# sapflow_pcb_v1.net
KiCad netlist of a schematic drawn in EAGLE
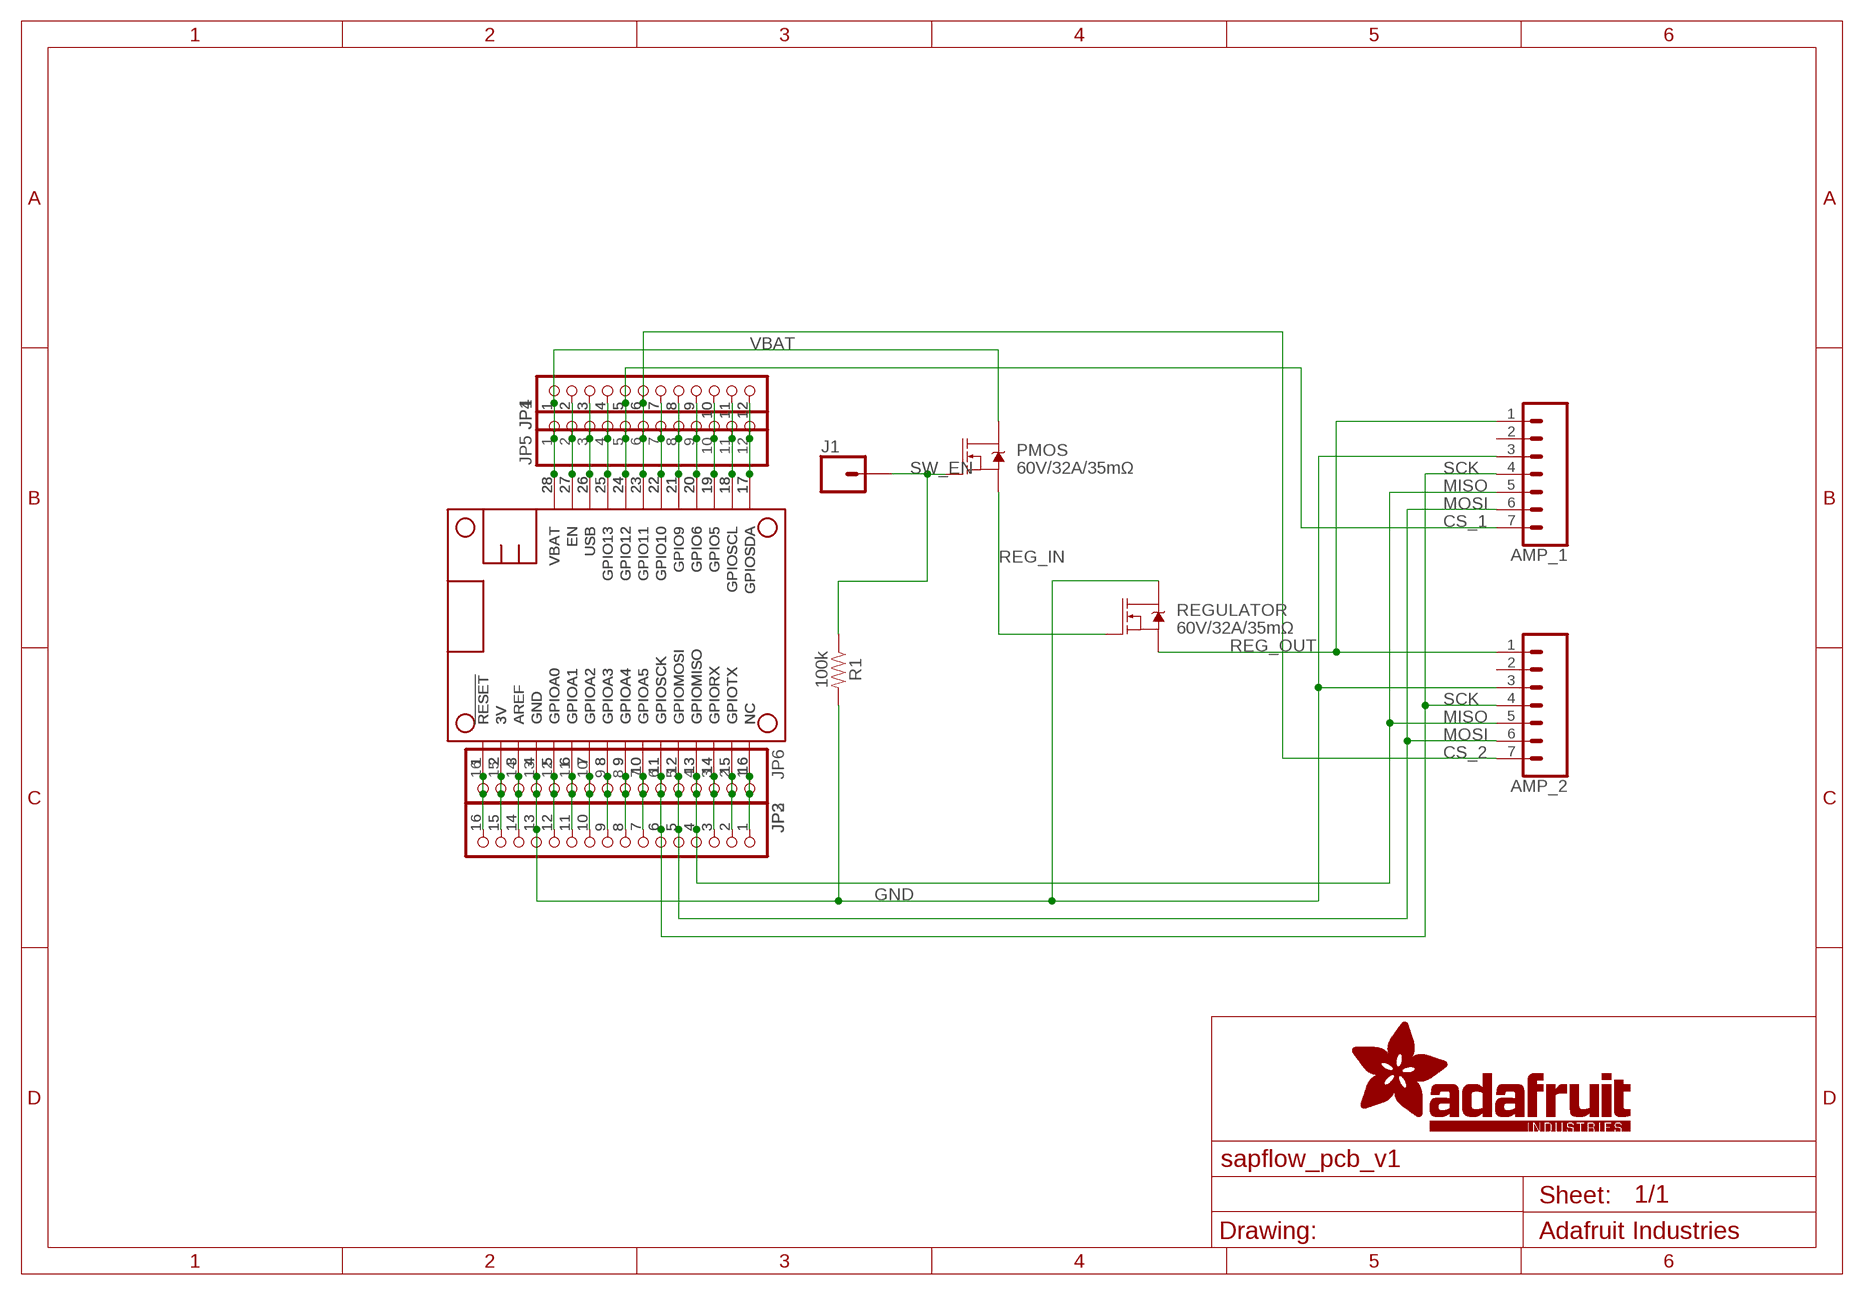
[diagram p0: schematic, sheet 1]

(export (version "E")
  (design (tool "Eeschema 10.0.6"))
  (components
    (comp (ref "AMP_1")
      (value "CONN_07")
      (footprint "eagle-import:1X07")
      (libsource (lib "eagle-import") (part "CONN_07"))
    )
    (comp (ref "AMP_2")
      (value "CONN_07")
      (footprint "eagle-import:1X07")
      (libsource (lib "eagle-import") (part "CONN_07"))
    )
    (comp (ref "J1")
      (value "CONN_01")
      (footprint "eagle-import:1X01")
      (libsource (lib "eagle-import") (part "CONN_01"))
    )
    (comp (ref "JP1")
      (value "HEADER-1X1276MIL")
      (footprint "eagle-import:1X12_ROUND_76MIL")
      (libsource (lib "eagle-import") (part "HEADER-1X1276MIL"))
    )
    (comp (ref "JP2")
      (value "HEADER-1X16_76MIL")
      (footprint "eagle-import:1X16_ROUND_76MIL")
      (libsource (lib "eagle-import") (part "HEADER-1X16_76MIL"))
    )
    (comp (ref "JP3")
      (value "HEADER-1X16_76MIL")
      (footprint "eagle-import:1X16_ROUND_76MIL")
      (libsource (lib "eagle-import") (part "HEADER-1X16_76MIL"))
    )
    (comp (ref "JP4")
      (value "HEADER-1X1276MIL")
      (footprint "eagle-import:1X12_ROUND_76MIL")
      (libsource (lib "eagle-import") (part "HEADER-1X1276MIL"))
    )
    (comp (ref "JP5")
      (value "HEADER-1X1276MIL")
      (footprint "eagle-import:1X12_ROUND_76MIL")
      (libsource (lib "eagle-import") (part "HEADER-1X1276MIL"))
    )
    (comp (ref "JP6")
      (value "HEADER-1X16_76MIL")
      (footprint "eagle-import:1X16_ROUND_76MIL")
      (libsource (lib "eagle-import") (part "HEADER-1X16_76MIL"))
    )
    (comp (ref "MS1")
      (value "FEATHERWING_NODIM")
      (footprint "eagle-import:FEATHERWING_DIM")
      (libsource (lib "eagle-import") (part "FEATHERWING_NODIM"))
    )
    (comp (ref "MS2")
      (value "FEATHERWING_NODIM")
      (footprint "eagle-import:FEATHERWING_DIM")
      (libsource (lib "eagle-import") (part "FEATHERWING_NODIM"))
    )
    (comp (ref "MS3")
      (value "FEATHERWING_NODIM")
      (footprint "eagle-import:FEATHERWING_DIM")
      (libsource (lib "eagle-import") (part "FEATHERWING_NODIM"))
    )
    (comp (ref "PMOS")
      (value "60V/32A/35mΩ")
      (footprint "eagle-import:TO220V")
      (libsource (lib "eagle-import") (part "MOSFET-NCH-FQP30N06L"))
    )
    (comp (ref "R1")
      (value "100k")
      (footprint "eagle-import:AXIAL-0.3")
      (libsource (lib "eagle-import") (part "100KOHM-HORIZ-1/4W-1%"))
    )
    (comp (ref "REGULATOR")
      (value "60V/32A/35mΩ")
      (footprint "eagle-import:TO220V")
      (libsource (lib "eagle-import") (part "MOSFET-NCH-FQP30N06L"))
    )
  )
  (nets
    (net (code "1") (name "/CS_1") (class "Default")
      (node (ref "AMP_1") (pin "7") (pinfunction "7_7") (pintype "passive"))
      (node (ref "JP1") (pin "5") (pinfunction "5_5") (pintype "passive"))
      (node (ref "JP4") (pin "5") (pinfunction "5_5") (pintype "passive"))
      (node (ref "JP5") (pin "5") (pinfunction "5_5") (pintype "passive"))
      (node (ref "MS1") (pin "24") (pinfunction "GPIO12_24") (pintype "bidirectional"))
      (node (ref "MS2") (pin "24") (pinfunction "GPIO12_24") (pintype "bidirectional"))
      (node (ref "MS3") (pin "24") (pinfunction "GPIO12_24") (pintype "bidirectional"))
    )
    (net (code "2") (name "/CS_2") (class "Default")
      (node (ref "AMP_2") (pin "7") (pinfunction "7_7") (pintype "passive"))
      (node (ref "JP1") (pin "6") (pinfunction "6_6") (pintype "passive"))
      (node (ref "JP4") (pin "6") (pinfunction "6_6") (pintype "passive"))
      (node (ref "JP5") (pin "6") (pinfunction "6_6") (pintype "passive"))
      (node (ref "MS1") (pin "23") (pinfunction "GPIO11_23") (pintype "bidirectional"))
      (node (ref "MS2") (pin "23") (pinfunction "GPIO11_23") (pintype "bidirectional"))
      (node (ref "MS3") (pin "23") (pinfunction "GPIO11_23") (pintype "bidirectional"))
    )
    (net (code "3") (name "/GND") (class "Default")
      (node (ref "AMP_1") (pin "3") (pinfunction "3_3") (pintype "passive"))
      (node (ref "AMP_2") (pin "3") (pinfunction "3_3") (pintype "passive"))
      (node (ref "JP2") (pin "13") (pinfunction "13_13") (pintype "passive"))
      (node (ref "JP3") (pin "13") (pinfunction "13_13") (pintype "passive"))
      (node (ref "JP6") (pin "13") (pinfunction "13_13") (pintype "passive"))
      (node (ref "MS1") (pin "4") (pinfunction "GND_4") (pintype "power_in"))
      (node (ref "MS2") (pin "4") (pinfunction "GND_4") (pintype "power_in"))
      (node (ref "MS3") (pin "4") (pinfunction "GND_4") (pintype "power_in"))
      (node (ref "R1") (pin "P$2") (pinfunction "2_P$2") (pintype "passive"))
      (node (ref "REGULATOR") (pin "2") (pinfunction "D_2") (pintype "bidirectional"))
    )
    (net (code "4") (name "/MISO") (class "Default")
      (node (ref "AMP_1") (pin "5") (pinfunction "5_5") (pintype "passive"))
      (node (ref "AMP_2") (pin "5") (pinfunction "5_5") (pintype "passive"))
      (node (ref "JP2") (pin "4") (pinfunction "4_4") (pintype "passive"))
      (node (ref "JP3") (pin "4") (pinfunction "4_4") (pintype "passive"))
      (node (ref "JP6") (pin "4") (pinfunction "4_4") (pintype "passive"))
      (node (ref "MS1") (pin "13") (pinfunction "GPIOMISO_13") (pintype "bidirectional"))
      (node (ref "MS2") (pin "13") (pinfunction "GPIOMISO_13") (pintype "bidirectional"))
      (node (ref "MS3") (pin "13") (pinfunction "GPIOMISO_13") (pintype "bidirectional"))
    )
    (net (code "5") (name "/MOSI") (class "Default")
      (node (ref "AMP_1") (pin "6") (pinfunction "6_6") (pintype "passive"))
      (node (ref "AMP_2") (pin "6") (pinfunction "6_6") (pintype "passive"))
      (node (ref "JP2") (pin "5") (pinfunction "5_5") (pintype "passive"))
      (node (ref "JP3") (pin "5") (pinfunction "5_5") (pintype "passive"))
      (node (ref "JP6") (pin "5") (pinfunction "5_5") (pintype "passive"))
      (node (ref "MS1") (pin "12") (pinfunction "GPIOMOSI_12") (pintype "bidirectional"))
      (node (ref "MS2") (pin "12") (pinfunction "GPIOMOSI_12") (pintype "bidirectional"))
      (node (ref "MS3") (pin "12") (pinfunction "GPIOMOSI_12") (pintype "bidirectional"))
    )
    (net (code "6") (name "/REG_IN") (class "Default")
      (node (ref "PMOS") (pin "3") (pinfunction "S_3") (pintype "bidirectional"))
      (node (ref "REGULATOR") (pin "1") (pinfunction "G_1") (pintype "bidirectional"))
    )
    (net (code "7") (name "/REG_OUT") (class "Default")
      (node (ref "AMP_1") (pin "1") (pinfunction "1_1") (pintype "passive"))
      (node (ref "AMP_2") (pin "1") (pinfunction "1_1") (pintype "passive"))
      (node (ref "REGULATOR") (pin "3") (pinfunction "S_3") (pintype "bidirectional"))
    )
    (net (code "8") (name "/SCK") (class "Default")
      (node (ref "AMP_1") (pin "4") (pinfunction "4_4") (pintype "passive"))
      (node (ref "AMP_2") (pin "4") (pinfunction "4_4") (pintype "passive"))
      (node (ref "JP2") (pin "6") (pinfunction "6_6") (pintype "passive"))
      (node (ref "JP3") (pin "6") (pinfunction "6_6") (pintype "passive"))
      (node (ref "JP6") (pin "6") (pinfunction "6_6") (pintype "passive"))
      (node (ref "MS1") (pin "11") (pinfunction "GPIOSCK_11") (pintype "bidirectional"))
      (node (ref "MS2") (pin "11") (pinfunction "GPIOSCK_11") (pintype "bidirectional"))
      (node (ref "MS3") (pin "11") (pinfunction "GPIOSCK_11") (pintype "bidirectional"))
    )
    (net (code "9") (name "/SW_EN") (class "Default")
      (node (ref "J1") (pin "1") (pinfunction "1_1") (pintype "passive"))
      (node (ref "PMOS") (pin "1") (pinfunction "G_1") (pintype "bidirectional"))
      (node (ref "R1") (pin "P$1") (pinfunction "1_P$1") (pintype "passive"))
    )
    (net (code "10") (name "/VBAT") (class "Default")
      (node (ref "JP1") (pin "1") (pinfunction "1_1") (pintype "passive"))
      (node (ref "JP4") (pin "1") (pinfunction "1_1") (pintype "passive"))
      (node (ref "JP5") (pin "1") (pinfunction "1_1") (pintype "passive"))
      (node (ref "MS1") (pin "28") (pinfunction "VBAT_28") (pintype "power_in"))
      (node (ref "MS2") (pin "28") (pinfunction "VBAT_28") (pintype "power_in"))
      (node (ref "MS3") (pin "28") (pinfunction "VBAT_28") (pintype "power_in"))
      (node (ref "PMOS") (pin "2") (pinfunction "D_2") (pintype "bidirectional"))
    )
    (net (code "11") (name "Net-(MS1-3V)") (class "Default")
      (node (ref "JP2") (pin "15") (pinfunction "15_15") (pintype "passive"))
      (node (ref "JP3") (pin "15") (pinfunction "15_15") (pintype "passive"))
      (node (ref "JP6") (pin "15") (pinfunction "15_15") (pintype "passive"))
      (node (ref "MS1") (pin "2") (pinfunction "3V_2") (pintype "power_in"))
      (node (ref "MS2") (pin "2") (pinfunction "3V_2") (pintype "power_in"))
      (node (ref "MS3") (pin "2") (pinfunction "3V_2") (pintype "power_in"))
    )
    (net (code "12") (name "Net-(MS1-AREF)") (class "Default")
      (node (ref "JP2") (pin "14") (pinfunction "14_14") (pintype "passive"))
      (node (ref "JP3") (pin "14") (pinfunction "14_14") (pintype "passive"))
      (node (ref "JP6") (pin "14") (pinfunction "14_14") (pintype "passive"))
      (node (ref "MS1") (pin "3") (pinfunction "AREF_3") (pintype "passive"))
      (node (ref "MS2") (pin "3") (pinfunction "AREF_3") (pintype "passive"))
      (node (ref "MS3") (pin "3") (pinfunction "AREF_3") (pintype "passive"))
    )
    (net (code "13") (name "Net-(MS1-EN)") (class "Default")
      (node (ref "JP1") (pin "2") (pinfunction "2_2") (pintype "passive"))
      (node (ref "JP4") (pin "2") (pinfunction "2_2") (pintype "passive"))
      (node (ref "JP5") (pin "2") (pinfunction "2_2") (pintype "passive"))
      (node (ref "MS1") (pin "27") (pinfunction "EN_27") (pintype "passive"))
      (node (ref "MS2") (pin "27") (pinfunction "EN_27") (pintype "passive"))
      (node (ref "MS3") (pin "27") (pinfunction "EN_27") (pintype "passive"))
    )
    (net (code "14") (name "Net-(MS1-GPIO5)") (class "Default")
      (node (ref "JP1") (pin "10") (pinfunction "10_10") (pintype "passive"))
      (node (ref "JP4") (pin "10") (pinfunction "10_10") (pintype "passive"))
      (node (ref "JP5") (pin "10") (pinfunction "10_10") (pintype "passive"))
      (node (ref "MS1") (pin "19") (pinfunction "GPIO5_19") (pintype "bidirectional"))
      (node (ref "MS2") (pin "19") (pinfunction "GPIO5_19") (pintype "bidirectional"))
      (node (ref "MS3") (pin "19") (pinfunction "GPIO5_19") (pintype "bidirectional"))
    )
    (net (code "15") (name "Net-(MS1-GPIO6)") (class "Default")
      (node (ref "JP1") (pin "9") (pinfunction "9_9") (pintype "passive"))
      (node (ref "JP4") (pin "9") (pinfunction "9_9") (pintype "passive"))
      (node (ref "JP5") (pin "9") (pinfunction "9_9") (pintype "passive"))
      (node (ref "MS1") (pin "20") (pinfunction "GPIO6_20") (pintype "bidirectional"))
      (node (ref "MS2") (pin "20") (pinfunction "GPIO6_20") (pintype "bidirectional"))
      (node (ref "MS3") (pin "20") (pinfunction "GPIO6_20") (pintype "bidirectional"))
    )
    (net (code "16") (name "Net-(MS1-GPIO9)") (class "Default")
      (node (ref "JP1") (pin "8") (pinfunction "8_8") (pintype "passive"))
      (node (ref "JP4") (pin "8") (pinfunction "8_8") (pintype "passive"))
      (node (ref "JP5") (pin "8") (pinfunction "8_8") (pintype "passive"))
      (node (ref "MS1") (pin "21") (pinfunction "GPIO9_21") (pintype "bidirectional"))
      (node (ref "MS2") (pin "21") (pinfunction "GPIO9_21") (pintype "bidirectional"))
      (node (ref "MS3") (pin "21") (pinfunction "GPIO9_21") (pintype "bidirectional"))
    )
    (net (code "17") (name "Net-(MS1-GPIO10)") (class "Default")
      (node (ref "JP1") (pin "7") (pinfunction "7_7") (pintype "passive"))
      (node (ref "JP4") (pin "7") (pinfunction "7_7") (pintype "passive"))
      (node (ref "JP5") (pin "7") (pinfunction "7_7") (pintype "passive"))
      (node (ref "MS1") (pin "22") (pinfunction "GPIO10_22") (pintype "bidirectional"))
      (node (ref "MS2") (pin "22") (pinfunction "GPIO10_22") (pintype "bidirectional"))
      (node (ref "MS3") (pin "22") (pinfunction "GPIO10_22") (pintype "bidirectional"))
    )
    (net (code "18") (name "Net-(MS1-GPIO13)") (class "Default")
      (node (ref "JP1") (pin "4") (pinfunction "4_4") (pintype "passive"))
      (node (ref "JP4") (pin "4") (pinfunction "4_4") (pintype "passive"))
      (node (ref "JP5") (pin "4") (pinfunction "4_4") (pintype "passive"))
      (node (ref "MS1") (pin "25") (pinfunction "GPIO13_25") (pintype "bidirectional"))
      (node (ref "MS2") (pin "25") (pinfunction "GPIO13_25") (pintype "bidirectional"))
      (node (ref "MS3") (pin "25") (pinfunction "GPIO13_25") (pintype "bidirectional"))
    )
    (net (code "19") (name "Net-(MS1-GPIOA0)") (class "Default")
      (node (ref "JP2") (pin "12") (pinfunction "12_12") (pintype "passive"))
      (node (ref "JP3") (pin "12") (pinfunction "12_12") (pintype "passive"))
      (node (ref "JP6") (pin "12") (pinfunction "12_12") (pintype "passive"))
      (node (ref "MS1") (pin "5") (pinfunction "GPIOA0_5") (pintype "bidirectional"))
      (node (ref "MS2") (pin "5") (pinfunction "GPIOA0_5") (pintype "bidirectional"))
      (node (ref "MS3") (pin "5") (pinfunction "GPIOA0_5") (pintype "bidirectional"))
    )
    (net (code "20") (name "Net-(MS1-GPIOA1)") (class "Default")
      (node (ref "JP2") (pin "11") (pinfunction "11_11") (pintype "passive"))
      (node (ref "JP3") (pin "11") (pinfunction "11_11") (pintype "passive"))
      (node (ref "JP6") (pin "11") (pinfunction "11_11") (pintype "passive"))
      (node (ref "MS1") (pin "6") (pinfunction "GPIOA1_6") (pintype "bidirectional"))
      (node (ref "MS2") (pin "6") (pinfunction "GPIOA1_6") (pintype "bidirectional"))
      (node (ref "MS3") (pin "6") (pinfunction "GPIOA1_6") (pintype "bidirectional"))
    )
    (net (code "21") (name "Net-(MS1-GPIOA2)") (class "Default")
      (node (ref "JP2") (pin "10") (pinfunction "10_10") (pintype "passive"))
      (node (ref "JP3") (pin "10") (pinfunction "10_10") (pintype "passive"))
      (node (ref "JP6") (pin "10") (pinfunction "10_10") (pintype "passive"))
      (node (ref "MS1") (pin "7") (pinfunction "GPIOA2_7") (pintype "bidirectional"))
      (node (ref "MS2") (pin "7") (pinfunction "GPIOA2_7") (pintype "bidirectional"))
      (node (ref "MS3") (pin "7") (pinfunction "GPIOA2_7") (pintype "bidirectional"))
    )
    (net (code "22") (name "Net-(MS1-GPIOA3)") (class "Default")
      (node (ref "JP2") (pin "9") (pinfunction "9_9") (pintype "passive"))
      (node (ref "JP3") (pin "9") (pinfunction "9_9") (pintype "passive"))
      (node (ref "JP6") (pin "9") (pinfunction "9_9") (pintype "passive"))
      (node (ref "MS1") (pin "8") (pinfunction "GPIOA3_8") (pintype "bidirectional"))
      (node (ref "MS2") (pin "8") (pinfunction "GPIOA3_8") (pintype "bidirectional"))
      (node (ref "MS3") (pin "8") (pinfunction "GPIOA3_8") (pintype "bidirectional"))
    )
    (net (code "23") (name "Net-(MS1-GPIOA4)") (class "Default")
      (node (ref "JP2") (pin "8") (pinfunction "8_8") (pintype "passive"))
      (node (ref "JP3") (pin "8") (pinfunction "8_8") (pintype "passive"))
      (node (ref "JP6") (pin "8") (pinfunction "8_8") (pintype "passive"))
      (node (ref "MS1") (pin "9") (pinfunction "GPIOA4_9") (pintype "bidirectional"))
      (node (ref "MS2") (pin "9") (pinfunction "GPIOA4_9") (pintype "bidirectional"))
      (node (ref "MS3") (pin "9") (pinfunction "GPIOA4_9") (pintype "bidirectional"))
    )
    (net (code "24") (name "Net-(MS1-GPIOA5)") (class "Default")
      (node (ref "JP2") (pin "7") (pinfunction "7_7") (pintype "passive"))
      (node (ref "JP3") (pin "7") (pinfunction "7_7") (pintype "passive"))
      (node (ref "JP6") (pin "7") (pinfunction "7_7") (pintype "passive"))
      (node (ref "MS1") (pin "10") (pinfunction "GPIOA5_10") (pintype "bidirectional"))
      (node (ref "MS2") (pin "10") (pinfunction "GPIOA5_10") (pintype "bidirectional"))
      (node (ref "MS3") (pin "10") (pinfunction "GPIOA5_10") (pintype "bidirectional"))
    )
    (net (code "25") (name "Net-(MS1-GPIORX)") (class "Default")
      (node (ref "JP2") (pin "3") (pinfunction "3_3") (pintype "passive"))
      (node (ref "JP3") (pin "3") (pinfunction "3_3") (pintype "passive"))
      (node (ref "JP6") (pin "3") (pinfunction "3_3") (pintype "passive"))
      (node (ref "MS1") (pin "14") (pinfunction "GPIORX_14") (pintype "bidirectional"))
      (node (ref "MS2") (pin "14") (pinfunction "GPIORX_14") (pintype "bidirectional"))
      (node (ref "MS3") (pin "14") (pinfunction "GPIORX_14") (pintype "bidirectional"))
    )
    (net (code "26") (name "Net-(MS1-GPIOSCL)") (class "Default")
      (node (ref "JP1") (pin "11") (pinfunction "11_11") (pintype "passive"))
      (node (ref "JP4") (pin "11") (pinfunction "11_11") (pintype "passive"))
      (node (ref "JP5") (pin "11") (pinfunction "11_11") (pintype "passive"))
      (node (ref "MS1") (pin "18") (pinfunction "GPIOSCL_18") (pintype "bidirectional"))
      (node (ref "MS2") (pin "18") (pinfunction "GPIOSCL_18") (pintype "bidirectional"))
      (node (ref "MS3") (pin "18") (pinfunction "GPIOSCL_18") (pintype "bidirectional"))
    )
    (net (code "27") (name "Net-(MS1-GPIOSDA)") (class "Default")
      (node (ref "JP1") (pin "12") (pinfunction "12_12") (pintype "passive"))
      (node (ref "JP4") (pin "12") (pinfunction "12_12") (pintype "passive"))
      (node (ref "JP5") (pin "12") (pinfunction "12_12") (pintype "passive"))
      (node (ref "MS1") (pin "17") (pinfunction "GPIOSDA_17") (pintype "bidirectional"))
      (node (ref "MS2") (pin "17") (pinfunction "GPIOSDA_17") (pintype "bidirectional"))
      (node (ref "MS3") (pin "17") (pinfunction "GPIOSDA_17") (pintype "bidirectional"))
    )
    (net (code "28") (name "Net-(MS1-GPIOTX)") (class "Default")
      (node (ref "JP2") (pin "2") (pinfunction "2_2") (pintype "passive"))
      (node (ref "JP3") (pin "2") (pinfunction "2_2") (pintype "passive"))
      (node (ref "JP6") (pin "2") (pinfunction "2_2") (pintype "passive"))
      (node (ref "MS1") (pin "15") (pinfunction "GPIOTX_15") (pintype "bidirectional"))
      (node (ref "MS2") (pin "15") (pinfunction "GPIOTX_15") (pintype "bidirectional"))
      (node (ref "MS3") (pin "15") (pinfunction "GPIOTX_15") (pintype "bidirectional"))
    )
    (net (code "29") (name "Net-(MS1-NC)") (class "Default")
      (node (ref "JP2") (pin "1") (pinfunction "1_1") (pintype "passive"))
      (node (ref "JP3") (pin "1") (pinfunction "1_1") (pintype "passive"))
      (node (ref "JP6") (pin "1") (pinfunction "1_1") (pintype "passive"))
      (node (ref "MS1") (pin "16") (pinfunction "NC_16") (pintype "passive"))
      (node (ref "MS2") (pin "16") (pinfunction "NC_16") (pintype "passive"))
      (node (ref "MS3") (pin "16") (pinfunction "NC_16") (pintype "passive"))
    )
    (net (code "30") (name "Net-(MS1-USB)") (class "Default")
      (node (ref "JP1") (pin "3") (pinfunction "3_3") (pintype "passive"))
      (node (ref "JP4") (pin "3") (pinfunction "3_3") (pintype "passive"))
      (node (ref "JP5") (pin "3") (pinfunction "3_3") (pintype "passive"))
      (node (ref "MS1") (pin "26") (pinfunction "USB_26") (pintype "power_in"))
      (node (ref "MS2") (pin "26") (pinfunction "USB_26") (pintype "power_in"))
      (node (ref "MS3") (pin "26") (pinfunction "USB_26") (pintype "power_in"))
    )
    (net (code "31") (name "Net-(MS1-~{RESET})") (class "Default")
      (node (ref "JP2") (pin "16") (pinfunction "16_16") (pintype "passive"))
      (node (ref "JP3") (pin "16") (pinfunction "16_16") (pintype "passive"))
      (node (ref "JP6") (pin "16") (pinfunction "16_16") (pintype "passive"))
      (node (ref "MS1") (pin "1") (pinfunction "~{RESET}_1") (pintype "input"))
      (node (ref "MS2") (pin "1") (pinfunction "~{RESET}_1") (pintype "input"))
      (node (ref "MS3") (pin "1") (pinfunction "~{RESET}_1") (pintype "input"))
    )
    (net (code "32") (name "unconnected-(AMP_1-Pad2)") (class "Default")
      (node (ref "AMP_1") (pin "2") (pinfunction "2_2") (pintype "passive"))
    )
    (net (code "33") (name "unconnected-(AMP_2-Pad2)") (class "Default")
      (node (ref "AMP_2") (pin "2") (pinfunction "2_2") (pintype "passive"))
    )
  )
)
